# SparkFun_6DoF_LSM6DSV16X.net
KiCad netlist of a schematic drawn in EAGLE
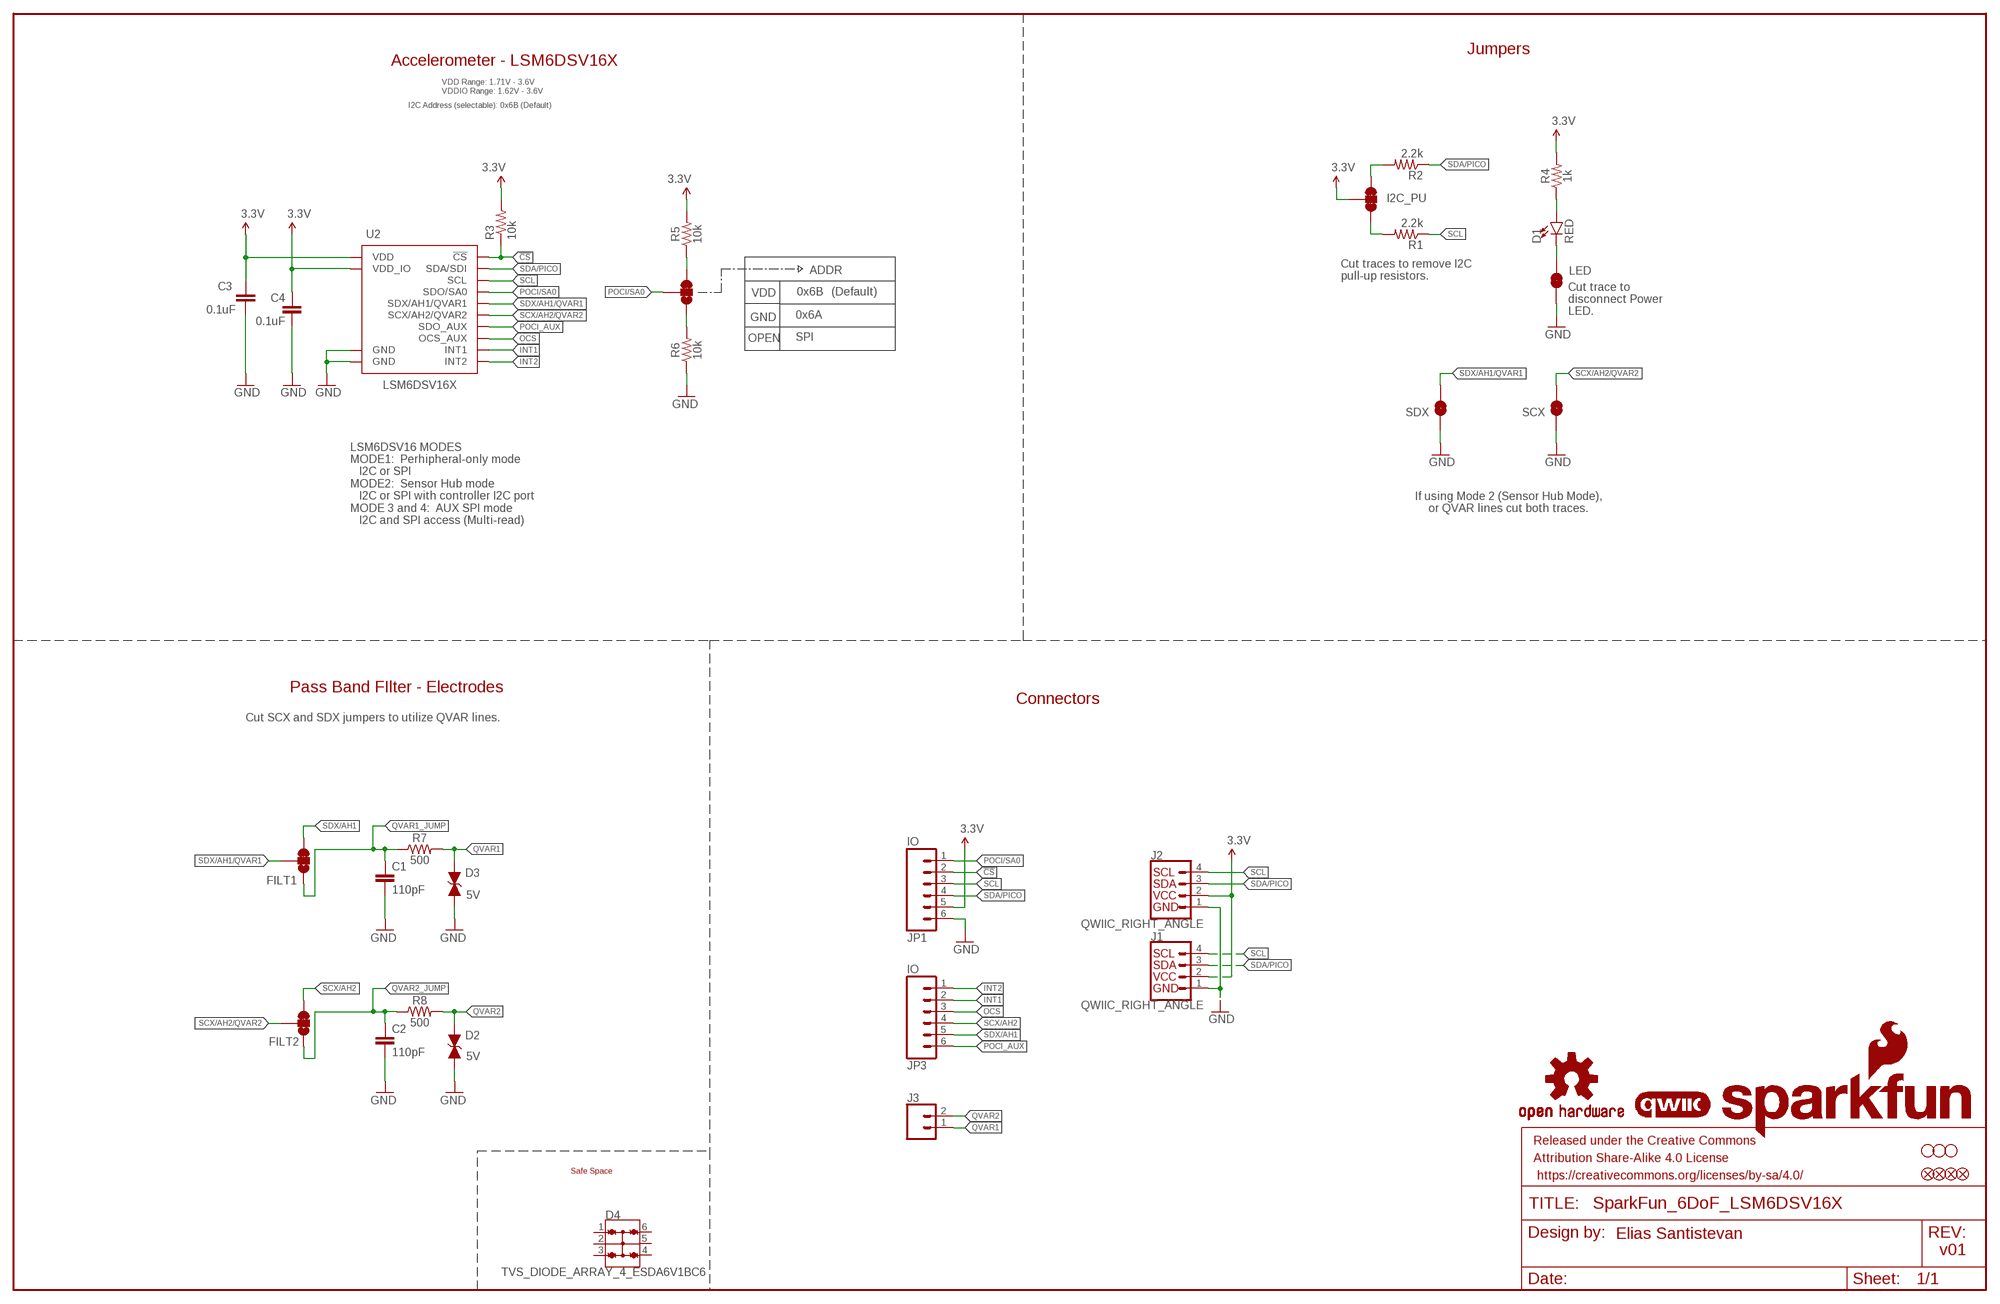
[diagram p0: schematic, sheet 1]

(export (version "E")
  (design (tool "Eeschema 10.0.6"))
  (components
    (comp (ref "ADDR")
      (value "JUMPER-SMT_3_1-NC_TRACE_SILK")
      (footprint "eagle-import:SMT-JUMPER_3_1-NC_TRACE_SILK")
      (libsource (lib "eagle-import") (part "JUMPER-SMT_3_1-NC_TRACE_SILK"))
    )
    (comp (ref "C1")
      (value "110pF")
      (footprint "eagle-import:0603")
      (libsource (lib "eagle-import") (part "110PF-0603-50V-5%"))
    )
    (comp (ref "C2")
      (value "110pF")
      (footprint "eagle-import:0603")
      (libsource (lib "eagle-import") (part "110PF-0603-50V-5%"))
    )
    (comp (ref "C3")
      (value "0.1uF")
      (footprint "eagle-import:0603")
      (libsource (lib "eagle-import") (part "0.1UF-0603-25V-(+80/-20%)"))
    )
    (comp (ref "C4")
      (value "0.1uF")
      (footprint "eagle-import:0603")
      (libsource (lib "eagle-import") (part "0.1UF-0603-25V-(+80/-20%)"))
    )
    (comp (ref "D1")
      (value "RED")
      (footprint "eagle-import:LED-0603")
      (libsource (lib "eagle-import") (part "LED-RED0603"))
    )
    (comp (ref "D2")
      (value "5V")
      (footprint "eagle-import:0603")
      (libsource (lib "eagle-import") (part "ESDALCL5-1BM2"))
    )
    (comp (ref "D3")
      (value "5V")
      (footprint "eagle-import:0603")
      (libsource (lib "eagle-import") (part "ESDALCL5-1BM2"))
    )
    (comp (ref "D4")
      (value "TVS_DIODE_ARRAY_4_ESDA6V1BC6")
      (footprint "eagle-import:SOT23-6L")
      (libsource (lib "eagle-import") (part "TVS_DIODE_ARRAY_4_ESDA6V1BC6"))
    )
    (comp (ref "FD1")
      (value "FIDUCIALUFIDUCIAL")
      (footprint "eagle-import:FIDUCIAL-MICRO")
      (libsource (lib "eagle-import") (part "FIDUCIALUFIDUCIAL"))
    )
    (comp (ref "FD2")
      (value "FIDUCIALUFIDUCIAL")
      (footprint "eagle-import:FIDUCIAL-MICRO")
      (libsource (lib "eagle-import") (part "FIDUCIALUFIDUCIAL"))
    )
    (comp (ref "FID1")
      (value "FIDUCIALUFIDUCIAL")
      (footprint "eagle-import:FIDUCIAL-MICRO")
      (libsource (lib "eagle-import") (part "FIDUCIALUFIDUCIAL"))
    )
    (comp (ref "FID2")
      (value "FIDUCIALUFIDUCIAL")
      (footprint "eagle-import:FIDUCIAL-MICRO")
      (libsource (lib "eagle-import") (part "FIDUCIALUFIDUCIAL"))
    )
    (comp (ref "FILT1")
      (value "JUMPER-SMT_3_1-NC_TRACE_SILK")
      (footprint "eagle-import:SMT-JUMPER_3_1-NC_TRACE_SILK")
      (libsource (lib "eagle-import") (part "JUMPER-SMT_3_1-NC_TRACE_SILK"))
    )
    (comp (ref "FILT2")
      (value "JUMPER-SMT_3_1-NC_TRACE_SILK")
      (footprint "eagle-import:SMT-JUMPER_3_1-NC_TRACE_SILK")
      (libsource (lib "eagle-import") (part "JUMPER-SMT_3_1-NC_TRACE_SILK"))
    )
    (comp (ref "FRAME2")
      (value "FRAME-LEDGER")
      (footprint "eagle-import:CREATIVE_COMMONS")
      (libsource (lib "eagle-import") (part "FRAME-LEDGER"))
    )
    (comp (ref "I2C_PU")
      (value "S_MODE")
      (footprint "eagle-import:SMT-JUMPER_3_2-NC_TRACE_SILK")
      (libsource (lib "eagle-import") (part "JUMPER-SMT_3_2-NC_TRACE_SILK"))
    )
    (comp (ref "J1")
      (value "QWIIC_RIGHT_ANGLE")
      (footprint "eagle-import:JST04_1MM_RA")
      (libsource (lib "eagle-import") (part "QWIIC_CONNECTORJS-1MM"))
    )
    (comp (ref "J2")
      (value "QWIIC_RIGHT_ANGLE")
      (footprint "eagle-import:JST04_1MM_RA")
      (libsource (lib "eagle-import") (part "QWIIC_CONNECTORJS-1MM"))
    )
    (comp (ref "J3")
      (value "CONN_021X02_NO_SILK")
      (footprint "eagle-import:1X02_NO_SILK")
      (libsource (lib "eagle-import") (part "CONN_021X02_NO_SILK"))
    )
    (comp (ref "JP1")
      (value "IO")
      (footprint "eagle-import:1X06_NO_SILK")
      (libsource (lib "eagle-import") (part "CONN_06NO_SILK_NO_POP"))
    )
    (comp (ref "JP3")
      (value "IO")
      (footprint "eagle-import:1X06_NO_SILK")
      (libsource (lib "eagle-import") (part "CONN_06NO_SILK_NO_POP"))
    )
    (comp (ref "LED")
      (value "JUMPER-SMT_2_NC_TRACE_SILK")
      (footprint "eagle-import:SMT-JUMPER_2_NC_TRACE_SILK")
      (libsource (lib "eagle-import") (part "JUMPER-SMT_2_NC_TRACE_SILK"))
    )
    (comp (ref "LOGO1")
      (value "QWIIC_LOGO_4MM")
      (footprint "eagle-import:QWIIC_4MM")
      (libsource (lib "eagle-import") (part "QWIIC_LOGO_4MM"))
    )
    (comp (ref "LOGO2")
      (value "OSHW-LOGOMINI")
      (footprint "eagle-import:OSHW-LOGO-MINI")
      (libsource (lib "eagle-import") (part "OSHW-LOGOMINI"))
    )
    (comp (ref "LOGO3")
      (value "SFE_LOGO_NAME_FLAME.1_INCH")
      (footprint "eagle-import:SFE_LOGO_NAME_FLAME_.1")
      (libsource (lib "eagle-import") (part "SFE_LOGO_NAME_FLAME.1_INCH"))
    )
    (comp (ref "R1")
      (value "2.2k")
      (footprint "eagle-import:0603")
      (libsource (lib "eagle-import") (part "2.2KOHM-0603-1/10W-1%"))
    )
    (comp (ref "R2")
      (value "2.2k")
      (footprint "eagle-import:0603")
      (libsource (lib "eagle-import") (part "2.2KOHM-0603-1/10W-1%"))
    )
    (comp (ref "R3")
      (value "10k")
      (footprint "eagle-import:0603")
      (libsource (lib "eagle-import") (part "10KOHM-0603-1/10W-1%"))
    )
    (comp (ref "R4")
      (value "1k")
      (footprint "eagle-import:0603")
      (libsource (lib "eagle-import") (part "1KOHM-0603-1/10W-1%"))
    )
    (comp (ref "R5")
      (value "10k")
      (footprint "eagle-import:0603")
      (libsource (lib "eagle-import") (part "10KOHM-0603-1/10W-1%"))
    )
    (comp (ref "R6")
      (value "10k")
      (footprint "eagle-import:0603")
      (libsource (lib "eagle-import") (part "10KOHM-0603-1/10W-1%"))
    )
    (comp (ref "R7")
      (value "500")
      (footprint "eagle-import:0603")
      (libsource (lib "eagle-import") (part "500OHM-0603-1/10W-1%"))
    )
    (comp (ref "R8")
      (value "500")
      (footprint "eagle-import:0603")
      (libsource (lib "eagle-import") (part "500OHM-0603-1/10W-1%"))
    )
    (comp (ref "SCX")
      (value "JUMPER-SMT_2_NC_TRACE_SILK")
      (footprint "eagle-import:SMT-JUMPER_2_NC_TRACE_SILK")
      (libsource (lib "eagle-import") (part "JUMPER-SMT_2_NC_TRACE_SILK"))
    )
    (comp (ref "SDX")
      (value "JUMPER-SMT_2_NC_TRACE_SILK")
      (footprint "eagle-import:SMT-JUMPER_2_NC_TRACE_SILK")
      (libsource (lib "eagle-import") (part "JUMPER-SMT_2_NC_TRACE_SILK"))
    )
    (comp (ref "STANDOFF1")
      (value "STAND-OFFTIGHT")
      (footprint "eagle-import:STAND-OFF-TIGHT")
      (libsource (lib "eagle-import") (part "STAND-OFFTIGHT"))
    )
    (comp (ref "STANDOFF2")
      (value "STAND-OFFTIGHT")
      (footprint "eagle-import:STAND-OFF-TIGHT")
      (libsource (lib "eagle-import") (part "STAND-OFFTIGHT"))
    )
    (comp (ref "STANDOFF3")
      (value "STAND-OFFTIGHT")
      (footprint "eagle-import:STAND-OFF-TIGHT")
      (libsource (lib "eagle-import") (part "STAND-OFFTIGHT"))
    )
    (comp (ref "U2")
      (value "LSM6DSV16X")
      (footprint "eagle-import:LGA-14L")
      (libsource (lib "eagle-import") (part "LSM6DSV16X"))
    )
  )
  (nets
    (net (code "1") (name "/~{CS}") (class "Default")
      (node (ref "JP1") (pin "2") (pinfunction "2_2") (pintype "passive"))
      (node (ref "R3") (pin "1") (pinfunction "1_1") (pintype "passive"))
      (node (ref "U2") (pin "P12") (pinfunction "~{CS}_P12") (pintype "bidirectional"))
    )
    (net (code "2") (name "3.3V") (class "Default")
      (node (ref "C3") (pin "1") (pinfunction "1_1") (pintype "passive"))
      (node (ref "C4") (pin "1") (pinfunction "1_1") (pintype "passive"))
      (node (ref "I2C_PU") (pin "2") (pinfunction "2_2") (pintype "passive"))
      (node (ref "J1") (pin "2") (pinfunction "2_2") (pintype "power_in"))
      (node (ref "J2") (pin "2") (pinfunction "2_2") (pintype "power_in"))
      (node (ref "JP1") (pin "5") (pinfunction "5_5") (pintype "passive"))
      (node (ref "R3") (pin "2") (pinfunction "2_2") (pintype "passive"))
      (node (ref "R4") (pin "2") (pinfunction "2_2") (pintype "passive"))
      (node (ref "R5") (pin "2") (pinfunction "2_2") (pintype "passive"))
      (node (ref "U2") (pin "P5") (pinfunction "VDD_IO_P5") (pintype "power_in"))
      (node (ref "U2") (pin "P8") (pinfunction "VDD_P8") (pintype "power_in"))
    )
    (net (code "3") (name "GND") (class "Default")
      (node (ref "C1") (pin "2") (pinfunction "2_2") (pintype "passive"))
      (node (ref "C2") (pin "2") (pinfunction "2_2") (pintype "passive"))
      (node (ref "C3") (pin "2") (pinfunction "2_2") (pintype "passive"))
      (node (ref "C4") (pin "2") (pinfunction "2_2") (pintype "passive"))
      (node (ref "D2") (pin "1") (pinfunction "A_1") (pintype "passive"))
      (node (ref "D3") (pin "1") (pinfunction "A_1") (pintype "passive"))
      (node (ref "J1") (pin "1") (pinfunction "1_1") (pintype "power_in"))
      (node (ref "J2") (pin "1") (pinfunction "1_1") (pintype "power_in"))
      (node (ref "JP1") (pin "6") (pinfunction "6_6") (pintype "passive"))
      (node (ref "LED") (pin "1") (pinfunction "1_1") (pintype "passive"))
      (node (ref "R6") (pin "1") (pinfunction "1_1") (pintype "passive"))
      (node (ref "SCX") (pin "1") (pinfunction "1_1") (pintype "passive"))
      (node (ref "SDX") (pin "1") (pinfunction "1_1") (pintype "passive"))
      (node (ref "U2") (pin "P6") (pinfunction "GND_P6") (pintype "power_in"))
      (node (ref "U2") (pin "P7") (pinfunction "GND_P7") (pintype "power_in"))
    )
    (net (code "4") (name "INT1") (class "Default")
      (node (ref "JP3") (pin "2") (pinfunction "2_2") (pintype "passive"))
      (node (ref "U2") (pin "P4") (pinfunction "INT1_P4") (pintype "bidirectional"))
    )
    (net (code "5") (name "INT2") (class "Default")
      (node (ref "JP3") (pin "1") (pinfunction "1_1") (pintype "passive"))
      (node (ref "U2") (pin "P9") (pinfunction "INT2_P9") (pintype "bidirectional"))
    )
    (net (code "6") (name "Net-(ADDR-Pad1)") (class "Default")
      (node (ref "ADDR") (pin "1") (pinfunction "1_1") (pintype "passive"))
      (node (ref "R6") (pin "2") (pinfunction "2_2") (pintype "passive"))
    )
    (net (code "7") (name "Net-(ADDR-Pad3)") (class "Default")
      (node (ref "ADDR") (pin "3") (pinfunction "3_3") (pintype "passive"))
      (node (ref "R5") (pin "1") (pinfunction "1_1") (pintype "passive"))
    )
    (net (code "8") (name "Net-(D1-PadA)") (class "Default")
      (node (ref "D1") (pin "A") (pinfunction "A_A") (pintype "passive"))
      (node (ref "R4") (pin "1") (pinfunction "1_1") (pintype "passive"))
    )
    (net (code "9") (name "Net-(D1-PadC)") (class "Default")
      (node (ref "D1") (pin "C") (pinfunction "C_C") (pintype "passive"))
      (node (ref "LED") (pin "2") (pinfunction "2_2") (pintype "passive"))
    )
    (net (code "10") (name "Net-(I2C_PU-Pad1)") (class "Default")
      (node (ref "I2C_PU") (pin "1") (pinfunction "1_1") (pintype "passive"))
      (node (ref "R1") (pin "2") (pinfunction "2_2") (pintype "passive"))
    )
    (net (code "11") (name "Net-(I2C_PU-Pad3)") (class "Default")
      (node (ref "I2C_PU") (pin "3") (pinfunction "3_3") (pintype "passive"))
      (node (ref "R2") (pin "2") (pinfunction "2_2") (pintype "passive"))
    )
    (net (code "12") (name "OCS") (class "Default")
      (node (ref "JP3") (pin "3") (pinfunction "3_3") (pintype "passive"))
      (node (ref "U2") (pin "P10") (pinfunction "OCS_AUX_P10") (pintype "bidirectional"))
    )
    (net (code "13") (name "POCI_AUX") (class "Default")
      (node (ref "JP3") (pin "6") (pinfunction "6_6") (pintype "passive"))
      (node (ref "U2") (pin "P11") (pinfunction "SDO_AUX_P11") (pintype "bidirectional"))
    )
    (net (code "14") (name "POCI{slash}SA0") (class "Default")
      (node (ref "ADDR") (pin "2") (pinfunction "2_2") (pintype "passive"))
      (node (ref "JP1") (pin "1") (pinfunction "1_1") (pintype "passive"))
      (node (ref "U2") (pin "P1") (pinfunction "SDO/SA0_P1") (pintype "bidirectional"))
    )
    (net (code "15") (name "QVAR1") (class "Default")
      (node (ref "D3") (pin "2") (pinfunction "C_2") (pintype "passive"))
      (node (ref "J3") (pin "1") (pinfunction "1_1") (pintype "passive"))
      (node (ref "R7") (pin "2") (pinfunction "2_2") (pintype "passive"))
    )
    (net (code "16") (name "QVAR1_JUMP") (class "Default")
      (node (ref "C1") (pin "1") (pinfunction "1_1") (pintype "passive"))
      (node (ref "FILT1") (pin "1") (pinfunction "1_1") (pintype "passive"))
      (node (ref "R7") (pin "1") (pinfunction "1_1") (pintype "passive"))
    )
    (net (code "17") (name "QVAR2") (class "Default")
      (node (ref "D2") (pin "2") (pinfunction "C_2") (pintype "passive"))
      (node (ref "J3") (pin "2") (pinfunction "2_2") (pintype "passive"))
      (node (ref "R8") (pin "2") (pinfunction "2_2") (pintype "passive"))
    )
    (net (code "18") (name "QVAR2_JUMP") (class "Default")
      (node (ref "C2") (pin "1") (pinfunction "1_1") (pintype "passive"))
      (node (ref "FILT2") (pin "1") (pinfunction "1_1") (pintype "passive"))
      (node (ref "R8") (pin "1") (pinfunction "1_1") (pintype "passive"))
    )
    (net (code "19") (name "SCL") (class "Default")
      (node (ref "J1") (pin "4") (pinfunction "4_4") (pintype "passive"))
      (node (ref "J2") (pin "4") (pinfunction "4_4") (pintype "passive"))
      (node (ref "JP1") (pin "3") (pinfunction "3_3") (pintype "passive"))
      (node (ref "R1") (pin "1") (pinfunction "1_1") (pintype "passive"))
      (node (ref "U2") (pin "P13") (pinfunction "SCL_P13") (pintype "bidirectional"))
    )
    (net (code "20") (name "SCX{slash}AH2") (class "Default")
      (node (ref "FILT2") (pin "3") (pinfunction "3_3") (pintype "passive"))
      (node (ref "JP3") (pin "4") (pinfunction "4_4") (pintype "passive"))
    )
    (net (code "21") (name "SCX{slash}AH2{slash}QVAR2") (class "Default")
      (node (ref "FILT2") (pin "2") (pinfunction "2_2") (pintype "passive"))
      (node (ref "SCX") (pin "2") (pinfunction "2_2") (pintype "passive"))
      (node (ref "U2") (pin "P3") (pinfunction "SCX/AH2/QVAR2_P3") (pintype "bidirectional"))
    )
    (net (code "22") (name "SDA{slash}PICO") (class "Default")
      (node (ref "J1") (pin "3") (pinfunction "3_3") (pintype "passive"))
      (node (ref "J2") (pin "3") (pinfunction "3_3") (pintype "passive"))
      (node (ref "JP1") (pin "4") (pinfunction "4_4") (pintype "passive"))
      (node (ref "R2") (pin "1") (pinfunction "1_1") (pintype "passive"))
      (node (ref "U2") (pin "P14") (pinfunction "SDA/SDI_P14") (pintype "bidirectional"))
    )
    (net (code "23") (name "SDX{slash}AH1") (class "Default")
      (node (ref "FILT1") (pin "3") (pinfunction "3_3") (pintype "passive"))
      (node (ref "JP3") (pin "5") (pinfunction "5_5") (pintype "passive"))
    )
    (net (code "24") (name "SDX{slash}AH1{slash}QVAR1") (class "Default")
      (node (ref "FILT1") (pin "2") (pinfunction "2_2") (pintype "passive"))
      (node (ref "SDX") (pin "2") (pinfunction "2_2") (pintype "passive"))
      (node (ref "U2") (pin "P2") (pinfunction "SDX/AH1/QVAR1_P2") (pintype "bidirectional"))
    )
    (net (code "25") (name "unconnected-(D4-Pad1)") (class "Default")
      (node (ref "D4") (pin "1") (pinfunction "1_1") (pintype "bidirectional"))
    )
    (net (code "26") (name "unconnected-(D4-Pad2)") (class "Default")
      (node (ref "D4") (pin "2") (pinfunction "2_2") (pintype "bidirectional"))
    )
    (net (code "27") (name "unconnected-(D4-Pad3)") (class "Default")
      (node (ref "D4") (pin "3") (pinfunction "3_3") (pintype "bidirectional"))
    )
    (net (code "28") (name "unconnected-(D4-Pad4)") (class "Default")
      (node (ref "D4") (pin "4") (pinfunction "4_4") (pintype "bidirectional"))
    )
    (net (code "29") (name "unconnected-(D4-Pad5)") (class "Default")
      (node (ref "D4") (pin "5") (pinfunction "5_5") (pintype "bidirectional"))
    )
    (net (code "30") (name "unconnected-(D4-Pad6)") (class "Default")
      (node (ref "D4") (pin "6") (pinfunction "6_6") (pintype "bidirectional"))
    )
  )
)
